# usbdmx.net
KiCad netlist of a schematic drawn in EAGLE
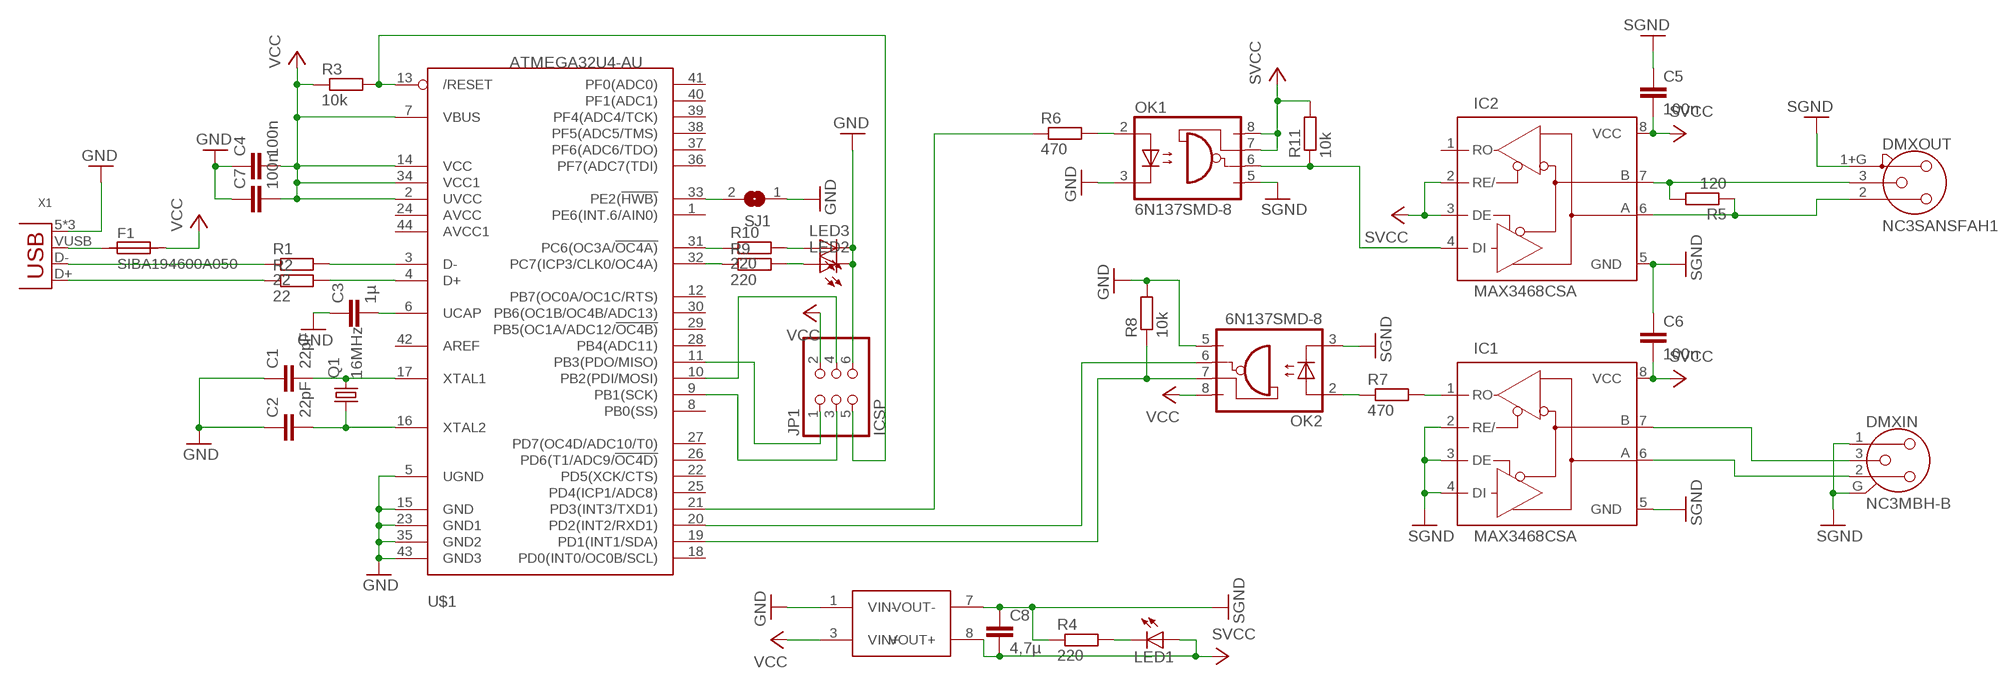
[diagram p0: schematic, sheet 1]

(export (version "E")
  (design (tool "Eeschema 10.0.6"))
  (components
    (comp (ref "C1")
      (value "22pF")
      (footprint "eagle-import:C0805")
      (libsource (lib "eagle-import") (part "C-EUC0805"))
    )
    (comp (ref "C2")
      (value "22pF")
      (footprint "eagle-import:C0805")
      (libsource (lib "eagle-import") (part "C-EUC0805"))
    )
    (comp (ref "C3")
      (value "1µ")
      (footprint "eagle-import:C0805")
      (libsource (lib "eagle-import") (part "C-EUC0805"))
    )
    (comp (ref "C4")
      (value "100n")
      (footprint "eagle-import:C0805")
      (libsource (lib "eagle-import") (part "C-EUC0805"))
    )
    (comp (ref "C5")
      (value "100n")
      (footprint "eagle-import:C0805")
      (libsource (lib "eagle-import") (part "C-EUC0805"))
    )
    (comp (ref "C6")
      (value "100n")
      (footprint "eagle-import:C0805")
      (libsource (lib "eagle-import") (part "C-EUC0805"))
    )
    (comp (ref "C7")
      (value "100n")
      (footprint "eagle-import:C0805")
      (libsource (lib "eagle-import") (part "C-EUC0805"))
    )
    (comp (ref "C8")
      (value "4,7µ")
      (footprint "eagle-import:C0805")
      (libsource (lib "eagle-import") (part "C-EUC0805"))
    )
    (comp (ref "DMXIN")
      (value "NC3MBH-B")
      (footprint "eagle-import:NC3MBH-B")
      (libsource (lib "eagle-import") (part "NC3MBH-B"))
    )
    (comp (ref "DMXOUT")
      (value "NC3SANSFAH1")
      (footprint "eagle-import:NC3FAH1")
      (libsource (lib "eagle-import") (part "NC3SANSFAH1"))
    )
    (comp (ref "F1")
      (value "SIBA194600A050")
      (footprint "eagle-import:1820")
      (libsource (lib "eagle-import") (part "SIBA194600A050"))
    )
    (comp (ref "IC1")
      (value "MAX3468CSA")
      (footprint "eagle-import:SO08")
      (fields (field (name "MPN") "MAX3468CSA+"))
      (libsource (lib "eagle-import") (part "MAX34SA68C"))
    )
    (comp (ref "IC2")
      (value "MAX3468CSA")
      (footprint "eagle-import:SO08")
      (fields (field (name "MPN") "MAX3468CSA+"))
      (libsource (lib "eagle-import") (part "MAX34SA68C"))
    )
    (comp (ref "JP1")
      (value "ICSP")
      (footprint "eagle-import:2X03SMD")
      (libsource (lib "eagle-import") (part "PINHD-2X3_2.54-SMD"))
    )
    (comp (ref "LED1")
      (value "LEDSML0603")
      (footprint "eagle-import:SML0603")
      (libsource (lib "eagle-import") (part "LEDSML0603"))
    )
    (comp (ref "LED2")
      (value "LEDSML0603")
      (footprint "eagle-import:SML0603")
      (libsource (lib "eagle-import") (part "LEDSML0603"))
    )
    (comp (ref "LED3")
      (value "LEDSML0603")
      (footprint "eagle-import:SML0603")
      (libsource (lib "eagle-import") (part "LEDSML0603"))
    )
    (comp (ref "OK1")
      (value "6N137SMD-8")
      (footprint "eagle-import:SMD8")
      (libsource (lib "eagle-import") (part "6N137SMD-8"))
    )
    (comp (ref "OK2")
      (value "6N137SMD-8")
      (footprint "eagle-import:SMD8")
      (libsource (lib "eagle-import") (part "6N137SMD-8"))
    )
    (comp (ref "Q1")
      (value "16MHz")
      (footprint "eagle-import:MT")
      (libsource (lib "eagle-import") (part "CRYSTALMT"))
    )
    (comp (ref "R1")
      (value "22")
      (footprint "eagle-import:R0805")
      (libsource (lib "eagle-import") (part "R-EU_R0805"))
    )
    (comp (ref "R2")
      (value "22")
      (footprint "eagle-import:R0805")
      (libsource (lib "eagle-import") (part "R-EU_R0805"))
    )
    (comp (ref "R3")
      (value "10k")
      (footprint "eagle-import:R0805")
      (libsource (lib "eagle-import") (part "R-EU_R0805"))
    )
    (comp (ref "R4")
      (value "220")
      (footprint "eagle-import:R0805")
      (libsource (lib "eagle-import") (part "R-EU_R0805"))
    )
    (comp (ref "R5")
      (value "120")
      (footprint "eagle-import:R0805")
      (libsource (lib "eagle-import") (part "R-EU_R0805"))
    )
    (comp (ref "R6")
      (value "470")
      (footprint "eagle-import:R0805")
      (libsource (lib "eagle-import") (part "R-EU_R0805"))
    )
    (comp (ref "R7")
      (value "470")
      (footprint "eagle-import:R0805")
      (libsource (lib "eagle-import") (part "R-EU_R0805"))
    )
    (comp (ref "R8")
      (value "10k")
      (footprint "eagle-import:R0805")
      (libsource (lib "eagle-import") (part "R-EU_R0805"))
    )
    (comp (ref "R9")
      (value "220")
      (footprint "eagle-import:R0805")
      (libsource (lib "eagle-import") (part "R-EU_R0805"))
    )
    (comp (ref "R10")
      (value "220")
      (footprint "eagle-import:R0805")
      (libsource (lib "eagle-import") (part "R-EU_R0805"))
    )
    (comp (ref "R11")
      (value "10k")
      (footprint "eagle-import:R0805")
      (libsource (lib "eagle-import") (part "R-EU_R0805"))
    )
    (comp (ref "SJ1") (value "SJ") (footprint "eagle-import:SJ") (libsource (lib "eagle-import") (part "SJ")))
    (comp (ref "U$1")
      (value "ATMEGA32U4-AU")
      (footprint "eagle-import:TQFP44")
      (libsource (lib "eagle-import") (part "ATMEGA32U4-AU"))
    )
    (comp (ref "U$2")
      (value "NTE0505SNTE0505MEC")
      (footprint "eagle-import:SMT")
      (libsource (lib "eagle-import") (part "NTE0505SNTE0505MEC"))
    )
    (comp (ref "X1")
      (value "USB-B-S-R")
      (footprint "eagle-import:USB-B-SMT-R")
      (libsource (lib "eagle-import") (part "USB-B-S-R"))
    )
  )
  (nets
    (net (code "1") (name "GND") (class "Default")
      (node (ref "C1") (pin "1") (pinfunction "1_1") (pintype "passive"))
      (node (ref "C2") (pin "1") (pinfunction "1_1") (pintype "passive"))
      (node (ref "C3") (pin "1") (pinfunction "1_1") (pintype "passive"))
      (node (ref "C4") (pin "1") (pinfunction "1_1") (pintype "passive"))
      (node (ref "C7") (pin "1") (pinfunction "1_1") (pintype "passive"))
      (node (ref "JP1") (pin "6") (pinfunction "6_6") (pintype "passive"))
      (node (ref "LED2") (pin "C") (pinfunction "C_C") (pintype "passive"))
      (node (ref "LED3") (pin "C") (pinfunction "C_C") (pintype "passive"))
      (node (ref "OK1") (pin "3") (pinfunction "C_3") (pintype "passive"))
      (node (ref "OK2") (pin "5") (pinfunction "GND_5") (pintype "passive"))
      (node (ref "R8") (pin "2") (pinfunction "2_2") (pintype "passive"))
      (node (ref "SJ1") (pin "1") (pinfunction "1_1") (pintype "passive"))
      (node (ref "U$1") (pin "15") (pinfunction "GND_15") (pintype "bidirectional"))
      (node (ref "U$1") (pin "23") (pinfunction "GND1_23") (pintype "bidirectional"))
      (node (ref "U$1") (pin "35") (pinfunction "GND2_35") (pintype "bidirectional"))
      (node (ref "U$1") (pin "43") (pinfunction "GND3_43") (pintype "bidirectional"))
      (node (ref "U$1") (pin "5") (pinfunction "UGND_5") (pintype "bidirectional"))
      (node (ref "U$2") (pin "1") (pinfunction "VIN-_1") (pintype "bidirectional"))
      (node (ref "X1") (pin "5") (pinfunction "GND_5") (pintype "bidirectional"))
      (node (ref "X1") (pin "6") (pinfunction "GND_6") (pintype "bidirectional"))
      (node (ref "X1") (pin "GND") (pinfunction "GND_GND") (pintype "bidirectional"))
    )
    (net (code "2") (name "Net-(IC1-A)") (class "Default")
      (node (ref "DMXIN") (pin "2") (pinfunction "2_2") (pintype "passive"))
      (node (ref "IC1") (pin "6") (pinfunction "A_6") (pintype "passive"))
    )
    (net (code "3") (name "Net-(IC1-B)") (class "Default")
      (node (ref "DMXIN") (pin "3") (pinfunction "3_3") (pintype "passive"))
      (node (ref "IC1") (pin "7") (pinfunction "B_7") (pintype "passive"))
    )
    (net (code "4") (name "Net-(IC1-RO)") (class "Default")
      (node (ref "IC1") (pin "1") (pinfunction "RO_1") (pintype "output"))
      (node (ref "R7") (pin "2") (pinfunction "2_2") (pintype "passive"))
    )
    (net (code "5") (name "Net-(IC2-A)") (class "Default")
      (node (ref "DMXOUT") (pin "2") (pinfunction "2_2") (pintype "passive"))
      (node (ref "IC2") (pin "6") (pinfunction "A_6") (pintype "passive"))
      (node (ref "R5") (pin "1") (pinfunction "1_1") (pintype "passive"))
    )
    (net (code "6") (name "Net-(IC2-B)") (class "Default")
      (node (ref "DMXOUT") (pin "3") (pinfunction "3_3") (pintype "passive"))
      (node (ref "IC2") (pin "7") (pinfunction "B_7") (pintype "passive"))
      (node (ref "R5") (pin "2") (pinfunction "2_2") (pintype "passive"))
    )
    (net (code "7") (name "Net-(IC2-DI)") (class "Default")
      (node (ref "IC2") (pin "4") (pinfunction "DI_4") (pintype "input"))
      (node (ref "OK1") (pin "6") (pinfunction "VO_6") (pintype "passive"))
      (node (ref "R11") (pin "1") (pinfunction "1_1") (pintype "passive"))
    )
    (net (code "8") (name "Net-(LED1-PadC)") (class "Default")
      (node (ref "LED1") (pin "C") (pinfunction "C_C") (pintype "passive"))
      (node (ref "R4") (pin "2") (pinfunction "2_2") (pintype "passive"))
    )
    (net (code "9") (name "Net-(LED2-PadA)") (class "Default")
      (node (ref "LED2") (pin "A") (pinfunction "A_A") (pintype "passive"))
      (node (ref "R9") (pin "2") (pinfunction "2_2") (pintype "passive"))
    )
    (net (code "10") (name "Net-(LED3-PadA)") (class "Default")
      (node (ref "LED3") (pin "A") (pinfunction "A_A") (pintype "passive"))
      (node (ref "R10") (pin "2") (pinfunction "2_2") (pintype "passive"))
    )
    (net (code "11") (name "Net-(OK1-A)") (class "Default")
      (node (ref "OK1") (pin "2") (pinfunction "A_2") (pintype "passive"))
      (node (ref "R6") (pin "2") (pinfunction "2_2") (pintype "passive"))
    )
    (net (code "12") (name "Net-(OK2-A)") (class "Default")
      (node (ref "OK2") (pin "2") (pinfunction "A_2") (pintype "passive"))
      (node (ref "R7") (pin "1") (pinfunction "1_1") (pintype "passive"))
    )
    (net (code "13") (name "Net-(OK2-VE)") (class "Default")
      (node (ref "OK2") (pin "7") (pinfunction "VE_7") (pintype "passive"))
      (node (ref "R8") (pin "1") (pinfunction "1_1") (pintype "passive"))
      (node (ref "U$1") (pin "19") (pinfunction "PD1(INT1/SDA)_19") (pintype "bidirectional"))
    )
    (net (code "14") (name "Net-(OK2-VO)") (class "Default")
      (node (ref "OK2") (pin "6") (pinfunction "VO_6") (pintype "passive"))
      (node (ref "U$1") (pin "20") (pinfunction "PD2(INT2/RXD1)_20") (pintype "bidirectional"))
    )
    (net (code "15") (name "Net-(Q1A-1)") (class "Default")
      (node (ref "C2") (pin "2") (pinfunction "2_2") (pintype "passive"))
      (node (ref "Q1") (pin "P1") (pinfunction "1_P1") (pintype "passive"))
      (node (ref "U$1") (pin "16") (pinfunction "XTAL2_16") (pintype "bidirectional"))
    )
    (net (code "16") (name "Net-(Q1A-2)") (class "Default")
      (node (ref "C1") (pin "2") (pinfunction "2_2") (pintype "passive"))
      (node (ref "Q1") (pin "P3") (pinfunction "2_P3") (pintype "passive"))
      (node (ref "U$1") (pin "17") (pinfunction "XTAL1_17") (pintype "bidirectional"))
    )
    (net (code "17") (name "Net-(R1-Pad1)") (class "Default")
      (node (ref "R1") (pin "1") (pinfunction "1_1") (pintype "passive"))
      (node (ref "X1") (pin "D-") (pinfunction "D-_D-") (pintype "bidirectional"))
    )
    (net (code "18") (name "Net-(R2-Pad1)") (class "Default")
      (node (ref "R2") (pin "1") (pinfunction "1_1") (pintype "passive"))
      (node (ref "X1") (pin "D+") (pinfunction "D+_D+") (pintype "bidirectional"))
    )
    (net (code "19") (name "Net-(U$1-D+)") (class "Default")
      (node (ref "R2") (pin "2") (pinfunction "2_2") (pintype "passive"))
      (node (ref "U$1") (pin "4") (pinfunction "D+_4") (pintype "bidirectional"))
    )
    (net (code "20") (name "Net-(U$1-D-)") (class "Default")
      (node (ref "R1") (pin "2") (pinfunction "2_2") (pintype "passive"))
      (node (ref "U$1") (pin "3") (pinfunction "D-_3") (pintype "bidirectional"))
    )
    (net (code "21") (name "Net-(U$1-PB1(SCK))") (class "Default")
      (node (ref "JP1") (pin "3") (pinfunction "3_3") (pintype "passive"))
      (node (ref "U$1") (pin "9") (pinfunction "PB1(SCK)_9") (pintype "bidirectional"))
    )
    (net (code "22") (name "Net-(U$1-PB2(PDI{slash}MOSI))") (class "Default")
      (node (ref "JP1") (pin "4") (pinfunction "4_4") (pintype "passive"))
      (node (ref "U$1") (pin "10") (pinfunction "PB2(PDI/MOSI)_10") (pintype "bidirectional"))
    )
    (net (code "23") (name "Net-(U$1-PB3(PDO{slash}MISO))") (class "Default")
      (node (ref "JP1") (pin "1") (pinfunction "1_1") (pintype "passive"))
      (node (ref "U$1") (pin "11") (pinfunction "PB3(PDO/MISO)_11") (pintype "bidirectional"))
    )
    (net (code "24") (name "Net-(U$1-PC6(OC3A{slash}~{OC4A}))") (class "Default")
      (node (ref "R10") (pin "1") (pinfunction "1_1") (pintype "passive"))
      (node (ref "U$1") (pin "31") (pinfunction "PC6(OC3A/~{OC4A})_31") (pintype "bidirectional"))
    )
    (net (code "25") (name "Net-(U$1-PC7(ICP3{slash}CLK0{slash}OC4A))") (class "Default")
      (node (ref "R9") (pin "1") (pinfunction "1_1") (pintype "passive"))
      (node (ref "U$1") (pin "32") (pinfunction "PC7(ICP3/CLK0/OC4A)_32") (pintype "bidirectional"))
    )
    (net (code "26") (name "Net-(U$1-PD3(INT3{slash}TXD1))") (class "Default")
      (node (ref "R6") (pin "1") (pinfunction "1_1") (pintype "passive"))
      (node (ref "U$1") (pin "21") (pinfunction "PD3(INT3/TXD1)_21") (pintype "bidirectional"))
    )
    (net (code "27") (name "Net-(U$1-PE2(~{HWB}))") (class "Default")
      (node (ref "SJ1") (pin "2") (pinfunction "2_2") (pintype "passive"))
      (node (ref "U$1") (pin "33") (pinfunction "PE2(~{HWB})_33") (pintype "bidirectional"))
    )
    (net (code "28") (name "Net-(U$1-UCAP)") (class "Default")
      (node (ref "C3") (pin "2") (pinfunction "2_2") (pintype "passive"))
      (node (ref "U$1") (pin "6") (pinfunction "UCAP_6") (pintype "bidirectional"))
    )
    (net (code "29") (name "Net-(U$1-{slash}RESET)") (class "Default")
      (node (ref "JP1") (pin "5") (pinfunction "5_5") (pintype "passive"))
      (node (ref "R3") (pin "2") (pinfunction "2_2") (pintype "passive"))
      (node (ref "U$1") (pin "13") (pinfunction "/RESET_13") (pintype "bidirectional"))
    )
    (net (code "30") (name "Net-(X1-VBUS)") (class "Default")
      (node (ref "F1") (pin "1") (pinfunction "1_1") (pintype "passive"))
      (node (ref "X1") (pin "VUSB") (pinfunction "VBUS_VUSB") (pintype "bidirectional"))
    )
    (net (code "31") (name "SGND") (class "Default")
      (node (ref "C5") (pin "1") (pinfunction "1_1") (pintype "passive"))
      (node (ref "C6") (pin "1") (pinfunction "1_1") (pintype "passive"))
      (node (ref "C8") (pin "1") (pinfunction "1_1") (pintype "passive"))
      (node (ref "DMXIN") (pin "1") (pinfunction "1_1") (pintype "passive"))
      (node (ref "DMXIN") (pin "G") (pinfunction "G_G") (pintype "passive"))
      (node (ref "DMXOUT") (pin "1+G") (pinfunction "1_1+G") (pintype "passive"))
      (node (ref "IC1") (pin "2") (pinfunction "RE/_2") (pintype "input"))
      (node (ref "IC1") (pin "3") (pinfunction "DE_3") (pintype "input"))
      (node (ref "IC1") (pin "4") (pinfunction "DI_4") (pintype "input"))
      (node (ref "IC1") (pin "5") (pinfunction "GND_5") (pintype "power_in"))
      (node (ref "IC2") (pin "5") (pinfunction "GND_5") (pintype "power_in"))
      (node (ref "OK1") (pin "5") (pinfunction "GND_5") (pintype "passive"))
      (node (ref "OK2") (pin "3") (pinfunction "C_3") (pintype "passive"))
      (node (ref "R4") (pin "1") (pinfunction "1_1") (pintype "passive"))
      (node (ref "U$2") (pin "7") (pinfunction "VOUT-_7") (pintype "bidirectional"))
    )
    (net (code "32") (name "SVCC") (class "Default")
      (node (ref "C5") (pin "2") (pinfunction "2_2") (pintype "passive"))
      (node (ref "C6") (pin "2") (pinfunction "2_2") (pintype "passive"))
      (node (ref "C8") (pin "2") (pinfunction "2_2") (pintype "passive"))
      (node (ref "IC1") (pin "8") (pinfunction "VCC_8") (pintype "power_in"))
      (node (ref "IC2") (pin "2") (pinfunction "RE/_2") (pintype "input"))
      (node (ref "IC2") (pin "3") (pinfunction "DE_3") (pintype "input"))
      (node (ref "IC2") (pin "8") (pinfunction "VCC_8") (pintype "power_in"))
      (node (ref "LED1") (pin "A") (pinfunction "A_A") (pintype "passive"))
      (node (ref "OK1") (pin "7") (pinfunction "VE_7") (pintype "passive"))
      (node (ref "OK1") (pin "8") (pinfunction "VCC_8") (pintype "passive"))
      (node (ref "R11") (pin "2") (pinfunction "2_2") (pintype "passive"))
      (node (ref "U$2") (pin "8") (pinfunction "VOUT+_8") (pintype "bidirectional"))
    )
    (net (code "33") (name "VCC") (class "Default")
      (node (ref "C4") (pin "2") (pinfunction "2_2") (pintype "passive"))
      (node (ref "C7") (pin "2") (pinfunction "2_2") (pintype "passive"))
      (node (ref "F1") (pin "2") (pinfunction "2_2") (pintype "passive"))
      (node (ref "JP1") (pin "2") (pinfunction "2_2") (pintype "passive"))
      (node (ref "OK2") (pin "8") (pinfunction "VCC_8") (pintype "passive"))
      (node (ref "R3") (pin "1") (pinfunction "1_1") (pintype "passive"))
      (node (ref "U$1") (pin "14") (pinfunction "VCC_14") (pintype "bidirectional"))
      (node (ref "U$1") (pin "2") (pinfunction "UVCC_2") (pintype "bidirectional"))
      (node (ref "U$1") (pin "34") (pinfunction "VCC1_34") (pintype "bidirectional"))
      (node (ref "U$1") (pin "7") (pinfunction "VBUS_7") (pintype "bidirectional"))
      (node (ref "U$2") (pin "3") (pinfunction "VIN+_3") (pintype "bidirectional"))
    )
    (net (code "34") (name "unconnected-(IC2-RO-Pad1)") (class "Default")
      (node (ref "IC2") (pin "1") (pinfunction "RO_1") (pintype "output"))
    )
    (net (code "35") (name "unconnected-(U$1-AREF-Pad42)") (class "Default")
      (node (ref "U$1") (pin "42") (pinfunction "AREF_42") (pintype "bidirectional"))
    )
    (net (code "36") (name "unconnected-(U$1-AVCC-Pad24)") (class "Default")
      (node (ref "U$1") (pin "24") (pinfunction "AVCC_24") (pintype "bidirectional"))
    )
    (net (code "37") (name "unconnected-(U$1-AVCC1-Pad44)") (class "Default")
      (node (ref "U$1") (pin "44") (pinfunction "AVCC1_44") (pintype "bidirectional"))
    )
    (net (code "38") (name "unconnected-(U$1-PB0(SS)-Pad8)") (class "Default")
      (node (ref "U$1") (pin "8") (pinfunction "PB0(SS)_8") (pintype "bidirectional"))
    )
    (net (code "39") (name "unconnected-(U$1-PB4(ADC11)-Pad28)") (class "Default")
      (node (ref "U$1") (pin "28") (pinfunction "PB4(ADC11)_28") (pintype "bidirectional"))
    )
    (net (code "40") (name "unconnected-(U$1-PB5(OC1A{slash}ADC12{slash}~{OC4B})-Pad29)") (class "Default")
      (node (ref "U$1") (pin "29") (pinfunction "PB5(OC1A/ADC12/~{OC4B})_29") (pintype "bidirectional"))
    )
    (net (code "41") (name "unconnected-(U$1-PB6(OC1B{slash}OC4B{slash}ADC13)-Pad30)") (class "Default")
      (node (ref "U$1") (pin "30") (pinfunction "PB6(OC1B/OC4B/ADC13)_30") (pintype "bidirectional"))
    )
    (net (code "42") (name "unconnected-(U$1-PB7(OC0A{slash}OC1C{slash}RTS)-Pad12)") (class "Default")
      (node (ref "U$1") (pin "12") (pinfunction "PB7(OC0A/OC1C/RTS)_12") (pintype "bidirectional"))
    )
    (net (code "43") (name "unconnected-(U$1-PD0(INT0{slash}OC0B{slash}SCL)-Pad18)") (class "Default")
      (node (ref "U$1") (pin "18") (pinfunction "PD0(INT0/OC0B/SCL)_18") (pintype "bidirectional"))
    )
    (net (code "44") (name "unconnected-(U$1-PD4(ICP1{slash}ADC8)-Pad25)") (class "Default")
      (node (ref "U$1") (pin "25") (pinfunction "PD4(ICP1/ADC8)_25") (pintype "bidirectional"))
    )
    (net (code "45") (name "unconnected-(U$1-PD5(XCK{slash}CTS)-Pad22)") (class "Default")
      (node (ref "U$1") (pin "22") (pinfunction "PD5(XCK/CTS)_22") (pintype "bidirectional"))
    )
    (net (code "46") (name "unconnected-(U$1-PD6(T1{slash}ADC9{slash}~{OC4D})-Pad26)") (class "Default")
      (node (ref "U$1") (pin "26") (pinfunction "PD6(T1/ADC9/~{OC4D})_26") (pintype "bidirectional"))
    )
    (net (code "47") (name "unconnected-(U$1-PD7(OC4D{slash}ADC10{slash}T0)-Pad27)") (class "Default")
      (node (ref "U$1") (pin "27") (pinfunction "PD7(OC4D/ADC10/T0)_27") (pintype "bidirectional"))
    )
    (net (code "48") (name "unconnected-(U$1-PE6(INT.6{slash}AIN0)-Pad1)") (class "Default")
      (node (ref "U$1") (pin "1") (pinfunction "PE6(INT.6/AIN0)_1") (pintype "bidirectional"))
    )
    (net (code "49") (name "unconnected-(U$1-PF0(ADC0)-Pad41)") (class "Default")
      (node (ref "U$1") (pin "41") (pinfunction "PF0(ADC0)_41") (pintype "bidirectional"))
    )
    (net (code "50") (name "unconnected-(U$1-PF1(ADC1)-Pad40)") (class "Default")
      (node (ref "U$1") (pin "40") (pinfunction "PF1(ADC1)_40") (pintype "bidirectional"))
    )
    (net (code "51") (name "unconnected-(U$1-PF4(ADC4{slash}TCK)-Pad39)") (class "Default")
      (node (ref "U$1") (pin "39") (pinfunction "PF4(ADC4/TCK)_39") (pintype "bidirectional"))
    )
    (net (code "52") (name "unconnected-(U$1-PF5(ADC5{slash}TMS)-Pad38)") (class "Default")
      (node (ref "U$1") (pin "38") (pinfunction "PF5(ADC5/TMS)_38") (pintype "bidirectional"))
    )
    (net (code "53") (name "unconnected-(U$1-PF6(ADC6{slash}TDO)-Pad37)") (class "Default")
      (node (ref "U$1") (pin "37") (pinfunction "PF6(ADC6/TDO)_37") (pintype "bidirectional"))
    )
    (net (code "54") (name "unconnected-(U$1-PF7(ADC7(TDI)-Pad36)") (class "Default")
      (node (ref "U$1") (pin "36") (pinfunction "PF7(ADC7(TDI)_36") (pintype "bidirectional"))
    )
  )
)
